# Cap_Piano_-_PCB.net
KiCad netlist of a schematic drawn in EAGLE
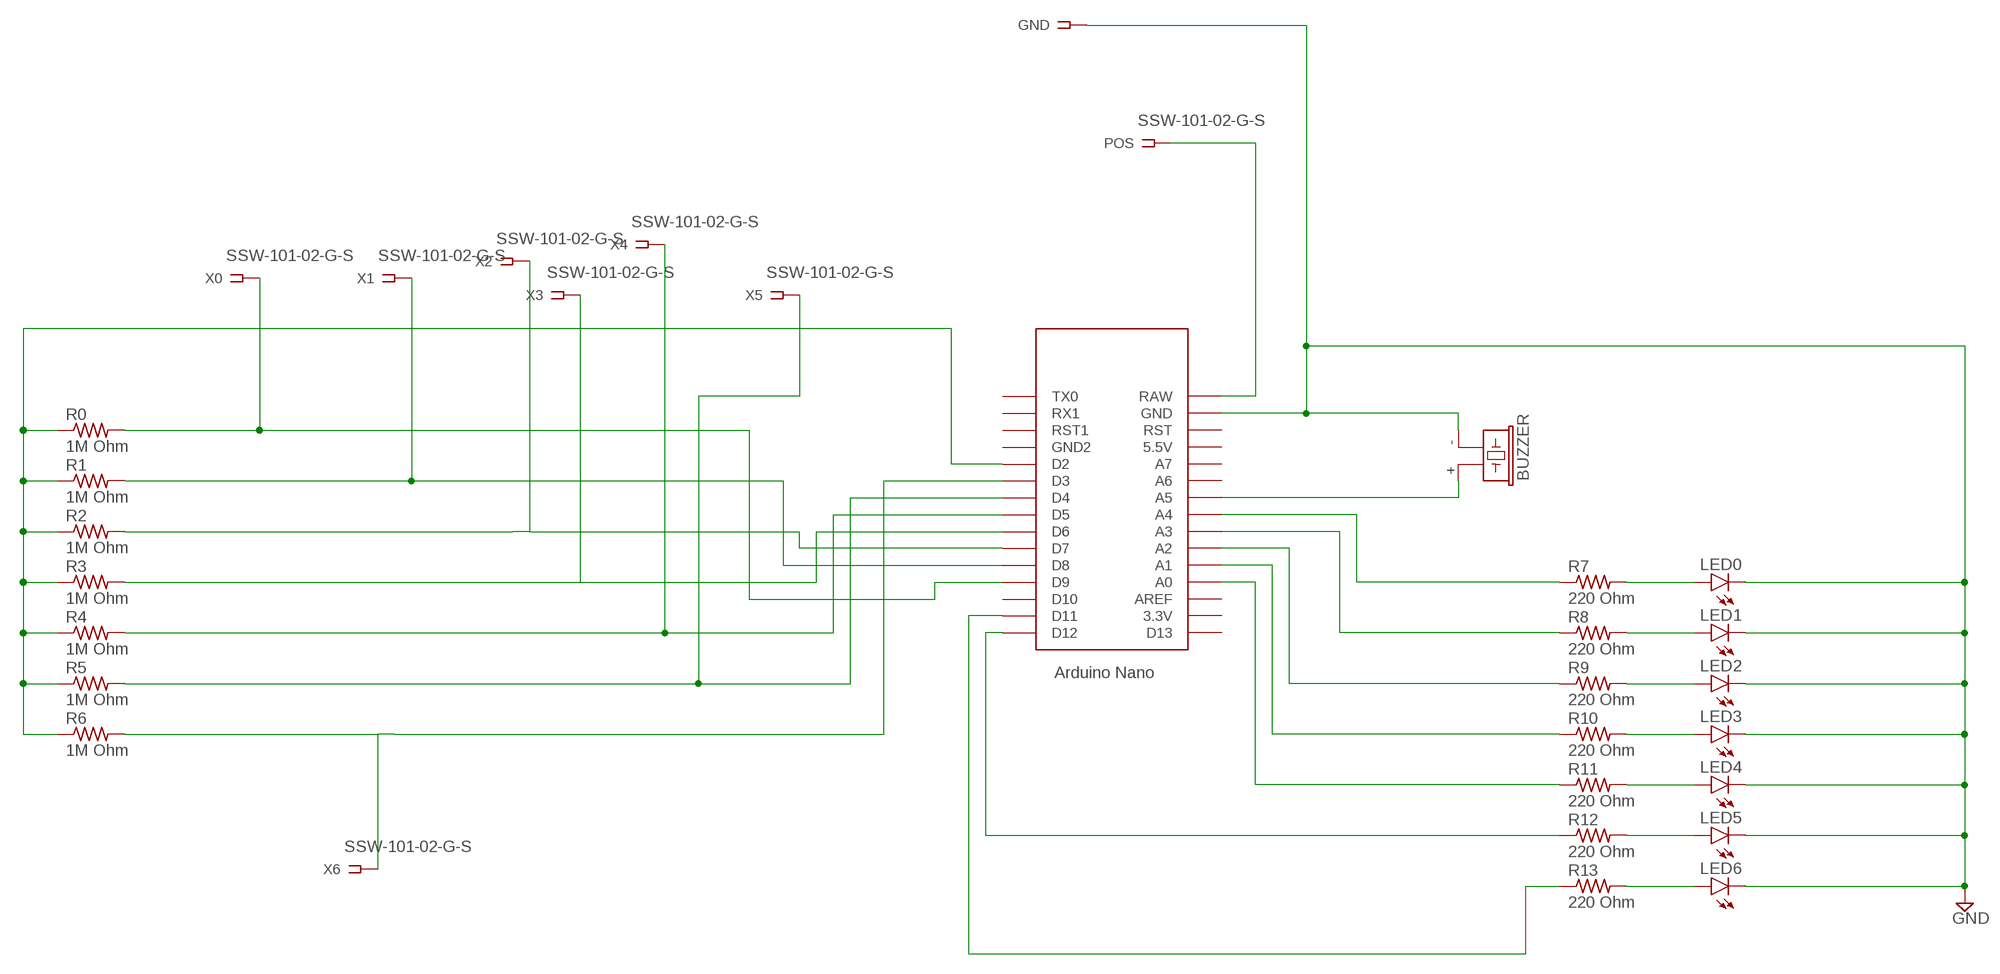
[diagram p0: schematic, sheet 1]

(export (version "E")
  (design (tool "Eeschema 10.0.6"))
  (components
    (comp (ref "BUZZER")
      (value "F/CM12P")
      (footprint "eagle-import:F_CM12P")
      (libsource (lib "eagle-import") (part "F/CM12P"))
    )
    (comp (ref "GND")
      (value "SSW-101-02-G-S")
      (footprint "eagle-import:SSW-101-02-G-S")
      (fields (field (name "MF") "Samtec Inc."))
      (libsource (lib "eagle-import") (part "SSW-101-02-G-S"))
    )
    (comp (ref "LED0")
      (value "LED5MM")
      (footprint "eagle-import:LED5MM")
      (libsource (lib "eagle-import") (part "LED5MM"))
    )
    (comp (ref "LED1")
      (value "LED5MM")
      (footprint "eagle-import:LED5MM")
      (libsource (lib "eagle-import") (part "LED5MM"))
    )
    (comp (ref "LED2")
      (value "LED5MM")
      (footprint "eagle-import:LED5MM")
      (libsource (lib "eagle-import") (part "LED5MM"))
    )
    (comp (ref "LED3")
      (value "LED5MM")
      (footprint "eagle-import:LED5MM")
      (libsource (lib "eagle-import") (part "LED5MM"))
    )
    (comp (ref "LED4")
      (value "LED5MM")
      (footprint "eagle-import:LED5MM")
      (libsource (lib "eagle-import") (part "LED5MM"))
    )
    (comp (ref "LED5")
      (value "LED5MM")
      (footprint "eagle-import:LED5MM")
      (libsource (lib "eagle-import") (part "LED5MM"))
    )
    (comp (ref "LED6")
      (value "LED5MM")
      (footprint "eagle-import:LED5MM")
      (libsource (lib "eagle-import") (part "LED5MM"))
    )
    (comp (ref "POS")
      (value "SSW-101-02-G-S")
      (footprint "eagle-import:SSW-101-02-G-S")
      (fields (field (name "MF") "Samtec Inc."))
      (libsource (lib "eagle-import") (part "SSW-101-02-G-S"))
    )
    (comp (ref "R0")
      (value "1M Ohm")
      (footprint "eagle-import:0207_12")
      (libsource (lib "eagle-import") (part "R-US_0207/12"))
    )
    (comp (ref "R1")
      (value "1M Ohm")
      (footprint "eagle-import:0207_12")
      (libsource (lib "eagle-import") (part "R-US_0207/12"))
    )
    (comp (ref "R2")
      (value "1M Ohm")
      (footprint "eagle-import:0207_12")
      (libsource (lib "eagle-import") (part "R-US_0207/12"))
    )
    (comp (ref "R3")
      (value "1M Ohm")
      (footprint "eagle-import:0207_12")
      (libsource (lib "eagle-import") (part "R-US_0207/12"))
    )
    (comp (ref "R4")
      (value "1M Ohm")
      (footprint "eagle-import:0207_12")
      (libsource (lib "eagle-import") (part "R-US_0207/12"))
    )
    (comp (ref "R5")
      (value "1M Ohm")
      (footprint "eagle-import:0207_12")
      (libsource (lib "eagle-import") (part "R-US_0207/12"))
    )
    (comp (ref "R6")
      (value "1M Ohm")
      (footprint "eagle-import:0207_12")
      (libsource (lib "eagle-import") (part "R-US_0207/12"))
    )
    (comp (ref "R7")
      (value "220 Ohm")
      (footprint "eagle-import:0207_12")
      (libsource (lib "eagle-import") (part "R-US_0207/12"))
    )
    (comp (ref "R8")
      (value "220 Ohm")
      (footprint "eagle-import:0207_12")
      (libsource (lib "eagle-import") (part "R-US_0207/12"))
    )
    (comp (ref "R9")
      (value "220 Ohm")
      (footprint "eagle-import:0207_12")
      (libsource (lib "eagle-import") (part "R-US_0207/12"))
    )
    (comp (ref "R10")
      (value "220 Ohm")
      (footprint "eagle-import:0207_12")
      (libsource (lib "eagle-import") (part "R-US_0207/12"))
    )
    (comp (ref "R11")
      (value "220 Ohm")
      (footprint "eagle-import:0207_12")
      (libsource (lib "eagle-import") (part "R-US_0207/12"))
    )
    (comp (ref "R12")
      (value "220 Ohm")
      (footprint "eagle-import:0207_12")
      (libsource (lib "eagle-import") (part "R-US_0207/12"))
    )
    (comp (ref "R13")
      (value "220 Ohm")
      (footprint "eagle-import:0207_12")
      (libsource (lib "eagle-import") (part "R-US_0207/12"))
    )
    (comp (ref "U$1")
      (value "NANO")
      (footprint "eagle-import:NANO")
      (libsource (lib "eagle-import") (part "NANO"))
    )
    (comp (ref "X0")
      (value "SSW-101-02-G-S")
      (footprint "eagle-import:SSW-101-02-G-S")
      (fields (field (name "MF") "Samtec Inc."))
      (libsource (lib "eagle-import") (part "SSW-101-02-G-S"))
    )
    (comp (ref "X1")
      (value "SSW-101-02-G-S")
      (footprint "eagle-import:SSW-101-02-G-S")
      (fields (field (name "MF") "Samtec Inc."))
      (libsource (lib "eagle-import") (part "SSW-101-02-G-S"))
    )
    (comp (ref "X2")
      (value "SSW-101-02-G-S")
      (footprint "eagle-import:SSW-101-02-G-S")
      (fields (field (name "MF") "Samtec Inc."))
      (libsource (lib "eagle-import") (part "SSW-101-02-G-S"))
    )
    (comp (ref "X3")
      (value "SSW-101-02-G-S")
      (footprint "eagle-import:SSW-101-02-G-S")
      (fields (field (name "MF") "Samtec Inc."))
      (libsource (lib "eagle-import") (part "SSW-101-02-G-S"))
    )
    (comp (ref "X4")
      (value "SSW-101-02-G-S")
      (footprint "eagle-import:SSW-101-02-G-S")
      (fields (field (name "MF") "Samtec Inc."))
      (libsource (lib "eagle-import") (part "SSW-101-02-G-S"))
    )
    (comp (ref "X5")
      (value "SSW-101-02-G-S")
      (footprint "eagle-import:SSW-101-02-G-S")
      (fields (field (name "MF") "Samtec Inc."))
      (libsource (lib "eagle-import") (part "SSW-101-02-G-S"))
    )
    (comp (ref "X6")
      (value "SSW-101-02-G-S")
      (footprint "eagle-import:SSW-101-02-G-S")
      (fields (field (name "MF") "Samtec Inc."))
      (libsource (lib "eagle-import") (part "SSW-101-02-G-S"))
    )
  )
  (nets
    (net (code "1") (name "GND") (class "Default")
      (node (ref "BUZZER") (pin "-") (pinfunction "2_-") (pintype "passive"))
      (node (ref "GND") (pin "1") (pinfunction "1_1") (pintype "passive"))
      (node (ref "LED0") (pin "K") (pinfunction "C_K") (pintype "passive"))
      (node (ref "LED1") (pin "K") (pinfunction "C_K") (pintype "passive"))
      (node (ref "LED2") (pin "K") (pinfunction "C_K") (pintype "passive"))
      (node (ref "LED3") (pin "K") (pinfunction "C_K") (pintype "passive"))
      (node (ref "LED4") (pin "K") (pinfunction "C_K") (pintype "passive"))
      (node (ref "LED5") (pin "K") (pinfunction "C_K") (pintype "passive"))
      (node (ref "LED6") (pin "K") (pinfunction "C_K") (pintype "passive"))
      (node (ref "U$1") (pin "GND") (pinfunction "GND_GND") (pintype "bidirectional"))
    )
    (net (code "2") (name "Net-(BUZZER-1)") (class "Default")
      (node (ref "BUZZER") (pin "+") (pinfunction "1_+") (pintype "passive"))
      (node (ref "U$1") (pin "A5") (pinfunction "A5_A5") (pintype "bidirectional"))
    )
    (net (code "3") (name "Net-(LED0-PadA)") (class "Default")
      (node (ref "LED0") (pin "A") (pinfunction "A_A") (pintype "passive"))
      (node (ref "R7") (pin "2") (pinfunction "2_2") (pintype "passive"))
    )
    (net (code "4") (name "Net-(LED1-PadA)") (class "Default")
      (node (ref "LED1") (pin "A") (pinfunction "A_A") (pintype "passive"))
      (node (ref "R8") (pin "2") (pinfunction "2_2") (pintype "passive"))
    )
    (net (code "5") (name "Net-(LED2-PadA)") (class "Default")
      (node (ref "LED2") (pin "A") (pinfunction "A_A") (pintype "passive"))
      (node (ref "R9") (pin "2") (pinfunction "2_2") (pintype "passive"))
    )
    (net (code "6") (name "Net-(LED3-PadA)") (class "Default")
      (node (ref "LED3") (pin "A") (pinfunction "A_A") (pintype "passive"))
      (node (ref "R10") (pin "2") (pinfunction "2_2") (pintype "passive"))
    )
    (net (code "7") (name "Net-(LED4-PadA)") (class "Default")
      (node (ref "LED4") (pin "A") (pinfunction "A_A") (pintype "passive"))
      (node (ref "R11") (pin "2") (pinfunction "2_2") (pintype "passive"))
    )
    (net (code "8") (name "Net-(LED5-PadA)") (class "Default")
      (node (ref "LED5") (pin "A") (pinfunction "A_A") (pintype "passive"))
      (node (ref "R12") (pin "2") (pinfunction "2_2") (pintype "passive"))
    )
    (net (code "9") (name "Net-(LED6-PadA)") (class "Default")
      (node (ref "LED6") (pin "A") (pinfunction "A_A") (pintype "passive"))
      (node (ref "R13") (pin "2") (pinfunction "2_2") (pintype "passive"))
    )
    (net (code "10") (name "Net-(POS-Pad1)") (class "Default")
      (node (ref "POS") (pin "1") (pinfunction "1_1") (pintype "passive"))
      (node (ref "U$1") (pin "RAW") (pinfunction "RAW_RAW") (pintype "bidirectional"))
    )
    (net (code "11") (name "Net-(R0-Pad1)") (class "Default")
      (node (ref "R0") (pin "1") (pinfunction "1_1") (pintype "passive"))
      (node (ref "R1") (pin "1") (pinfunction "1_1") (pintype "passive"))
      (node (ref "R2") (pin "1") (pinfunction "1_1") (pintype "passive"))
      (node (ref "R3") (pin "1") (pinfunction "1_1") (pintype "passive"))
      (node (ref "R4") (pin "1") (pinfunction "1_1") (pintype "passive"))
      (node (ref "R5") (pin "1") (pinfunction "1_1") (pintype "passive"))
      (node (ref "R6") (pin "1") (pinfunction "1_1") (pintype "passive"))
      (node (ref "U$1") (pin "D2") (pinfunction "D2_D2") (pintype "bidirectional"))
    )
    (net (code "12") (name "Net-(R0-Pad2)") (class "Default")
      (node (ref "R0") (pin "2") (pinfunction "2_2") (pintype "passive"))
      (node (ref "U$1") (pin "D9") (pinfunction "D9_D9") (pintype "bidirectional"))
      (node (ref "X0") (pin "1") (pinfunction "1_1") (pintype "passive"))
    )
    (net (code "13") (name "Net-(R1-Pad2)") (class "Default")
      (node (ref "R1") (pin "2") (pinfunction "2_2") (pintype "passive"))
      (node (ref "U$1") (pin "D8") (pinfunction "D8_D8") (pintype "bidirectional"))
      (node (ref "X1") (pin "1") (pinfunction "1_1") (pintype "passive"))
    )
    (net (code "14") (name "Net-(R2-Pad2)") (class "Default")
      (node (ref "R2") (pin "2") (pinfunction "2_2") (pintype "passive"))
      (node (ref "U$1") (pin "D7") (pinfunction "D7_D7") (pintype "bidirectional"))
      (node (ref "X2") (pin "1") (pinfunction "1_1") (pintype "passive"))
    )
    (net (code "15") (name "Net-(R3-Pad2)") (class "Default")
      (node (ref "R3") (pin "2") (pinfunction "2_2") (pintype "passive"))
      (node (ref "U$1") (pin "D6") (pinfunction "D6_D6") (pintype "bidirectional"))
      (node (ref "X3") (pin "1") (pinfunction "1_1") (pintype "passive"))
    )
    (net (code "16") (name "Net-(R4-Pad2)") (class "Default")
      (node (ref "R4") (pin "2") (pinfunction "2_2") (pintype "passive"))
      (node (ref "U$1") (pin "D5") (pinfunction "D5_D5") (pintype "bidirectional"))
      (node (ref "X4") (pin "1") (pinfunction "1_1") (pintype "passive"))
    )
    (net (code "17") (name "Net-(R5-Pad2)") (class "Default")
      (node (ref "R5") (pin "2") (pinfunction "2_2") (pintype "passive"))
      (node (ref "U$1") (pin "D4") (pinfunction "D4_D4") (pintype "bidirectional"))
      (node (ref "X5") (pin "1") (pinfunction "1_1") (pintype "passive"))
    )
    (net (code "18") (name "Net-(R6-Pad2)") (class "Default")
      (node (ref "R6") (pin "2") (pinfunction "2_2") (pintype "passive"))
      (node (ref "U$1") (pin "D3") (pinfunction "D3_D3") (pintype "bidirectional"))
      (node (ref "X6") (pin "1") (pinfunction "1_1") (pintype "passive"))
    )
    (net (code "19") (name "Net-(R7-Pad1)") (class "Default")
      (node (ref "R7") (pin "1") (pinfunction "1_1") (pintype "passive"))
      (node (ref "U$1") (pin "A4") (pinfunction "A4_A4") (pintype "bidirectional"))
    )
    (net (code "20") (name "Net-(R8-Pad1)") (class "Default")
      (node (ref "R8") (pin "1") (pinfunction "1_1") (pintype "passive"))
      (node (ref "U$1") (pin "A3") (pinfunction "A3_A3") (pintype "bidirectional"))
    )
    (net (code "21") (name "Net-(R9-Pad1)") (class "Default")
      (node (ref "R9") (pin "1") (pinfunction "1_1") (pintype "passive"))
      (node (ref "U$1") (pin "A2") (pinfunction "A2_A2") (pintype "bidirectional"))
    )
    (net (code "22") (name "Net-(R10-Pad1)") (class "Default")
      (node (ref "R10") (pin "1") (pinfunction "1_1") (pintype "passive"))
      (node (ref "U$1") (pin "A1") (pinfunction "A1_A1") (pintype "bidirectional"))
    )
    (net (code "23") (name "Net-(R11-Pad1)") (class "Default")
      (node (ref "R11") (pin "1") (pinfunction "1_1") (pintype "passive"))
      (node (ref "U$1") (pin "A0") (pinfunction "A0_A0") (pintype "bidirectional"))
    )
    (net (code "24") (name "Net-(R12-Pad1)") (class "Default")
      (node (ref "R12") (pin "1") (pinfunction "1_1") (pintype "passive"))
      (node (ref "U$1") (pin "D12") (pinfunction "D12_D12") (pintype "bidirectional"))
    )
    (net (code "25") (name "Net-(R13-Pad1)") (class "Default")
      (node (ref "R13") (pin "1") (pinfunction "1_1") (pintype "passive"))
      (node (ref "U$1") (pin "D11") (pinfunction "D11_D11") (pintype "bidirectional"))
    )
    (net (code "26") (name "unconnected-(U$1-5.5V-Pad5V)") (class "Default")
      (node (ref "U$1") (pin "5V") (pinfunction "5.5V_5V") (pintype "bidirectional"))
    )
    (net (code "27") (name "unconnected-(U$1-GND2-PadGND1)") (class "Default")
      (node (ref "U$1") (pin "GND1") (pinfunction "GND2_GND1") (pintype "bidirectional"))
    )
    (net (code "28") (name "unconnected-(U$1-Pad3.3V)") (class "Default")
      (node (ref "U$1") (pin "3.3V") (pinfunction "3.3V_3.3V") (pintype "bidirectional"))
    )
    (net (code "29") (name "unconnected-(U$1-PadA6)") (class "Default")
      (node (ref "U$1") (pin "A6") (pinfunction "A6_A6") (pintype "bidirectional"))
    )
    (net (code "30") (name "unconnected-(U$1-PadA7)") (class "Default")
      (node (ref "U$1") (pin "A7") (pinfunction "A7_A7") (pintype "bidirectional"))
    )
    (net (code "31") (name "unconnected-(U$1-PadAREF)") (class "Default")
      (node (ref "U$1") (pin "AREF") (pinfunction "AREF_AREF") (pintype "bidirectional"))
    )
    (net (code "32") (name "unconnected-(U$1-PadD10)") (class "Default")
      (node (ref "U$1") (pin "D10") (pinfunction "D10_D10") (pintype "bidirectional"))
    )
    (net (code "33") (name "unconnected-(U$1-PadD13)") (class "Default")
      (node (ref "U$1") (pin "D13") (pinfunction "D13_D13") (pintype "bidirectional"))
    )
    (net (code "34") (name "unconnected-(U$1-PadICSP1)") (class "Default")
      (node (ref "U$1") (pin "ICSP1") (pinfunction "ICSP1_ICSP1") (pintype "bidirectional"))
    )
    (net (code "35") (name "unconnected-(U$1-PadICSP2)") (class "Default")
      (node (ref "U$1") (pin "ICSP2") (pinfunction "ICSP2_ICSP2") (pintype "bidirectional"))
    )
    (net (code "36") (name "unconnected-(U$1-PadICSP3)") (class "Default")
      (node (ref "U$1") (pin "ICSP3") (pinfunction "ICSP3_ICSP3") (pintype "bidirectional"))
    )
    (net (code "37") (name "unconnected-(U$1-PadICSP4)") (class "Default")
      (node (ref "U$1") (pin "ICSP4") (pinfunction "ICSP4_ICSP4") (pintype "bidirectional"))
    )
    (net (code "38") (name "unconnected-(U$1-PadICSP5)") (class "Default")
      (node (ref "U$1") (pin "ICSP5") (pinfunction "ICSP5_ICSP5") (pintype "bidirectional"))
    )
    (net (code "39") (name "unconnected-(U$1-PadICSP6)") (class "Default")
      (node (ref "U$1") (pin "ICSP6") (pinfunction "ICSP6_ICSP6") (pintype "bidirectional"))
    )
    (net (code "40") (name "unconnected-(U$1-PadRST)") (class "Default")
      (node (ref "U$1") (pin "RST") (pinfunction "RST_RST") (pintype "bidirectional"))
    )
    (net (code "41") (name "unconnected-(U$1-PadRST1)") (class "Default")
      (node (ref "U$1") (pin "RST1") (pinfunction "RST1_RST1") (pintype "bidirectional"))
    )
    (net (code "42") (name "unconnected-(U$1-PadRX1)") (class "Default")
      (node (ref "U$1") (pin "RX1") (pinfunction "RX1_RX1") (pintype "bidirectional"))
    )
    (net (code "43") (name "unconnected-(U$1-PadTX0)") (class "Default")
      (node (ref "U$1") (pin "TX0") (pinfunction "TX0_TX0") (pintype "bidirectional"))
    )
  )
)
